# pcb_telemetria.net
KiCad netlist of a schematic drawn in EAGLE
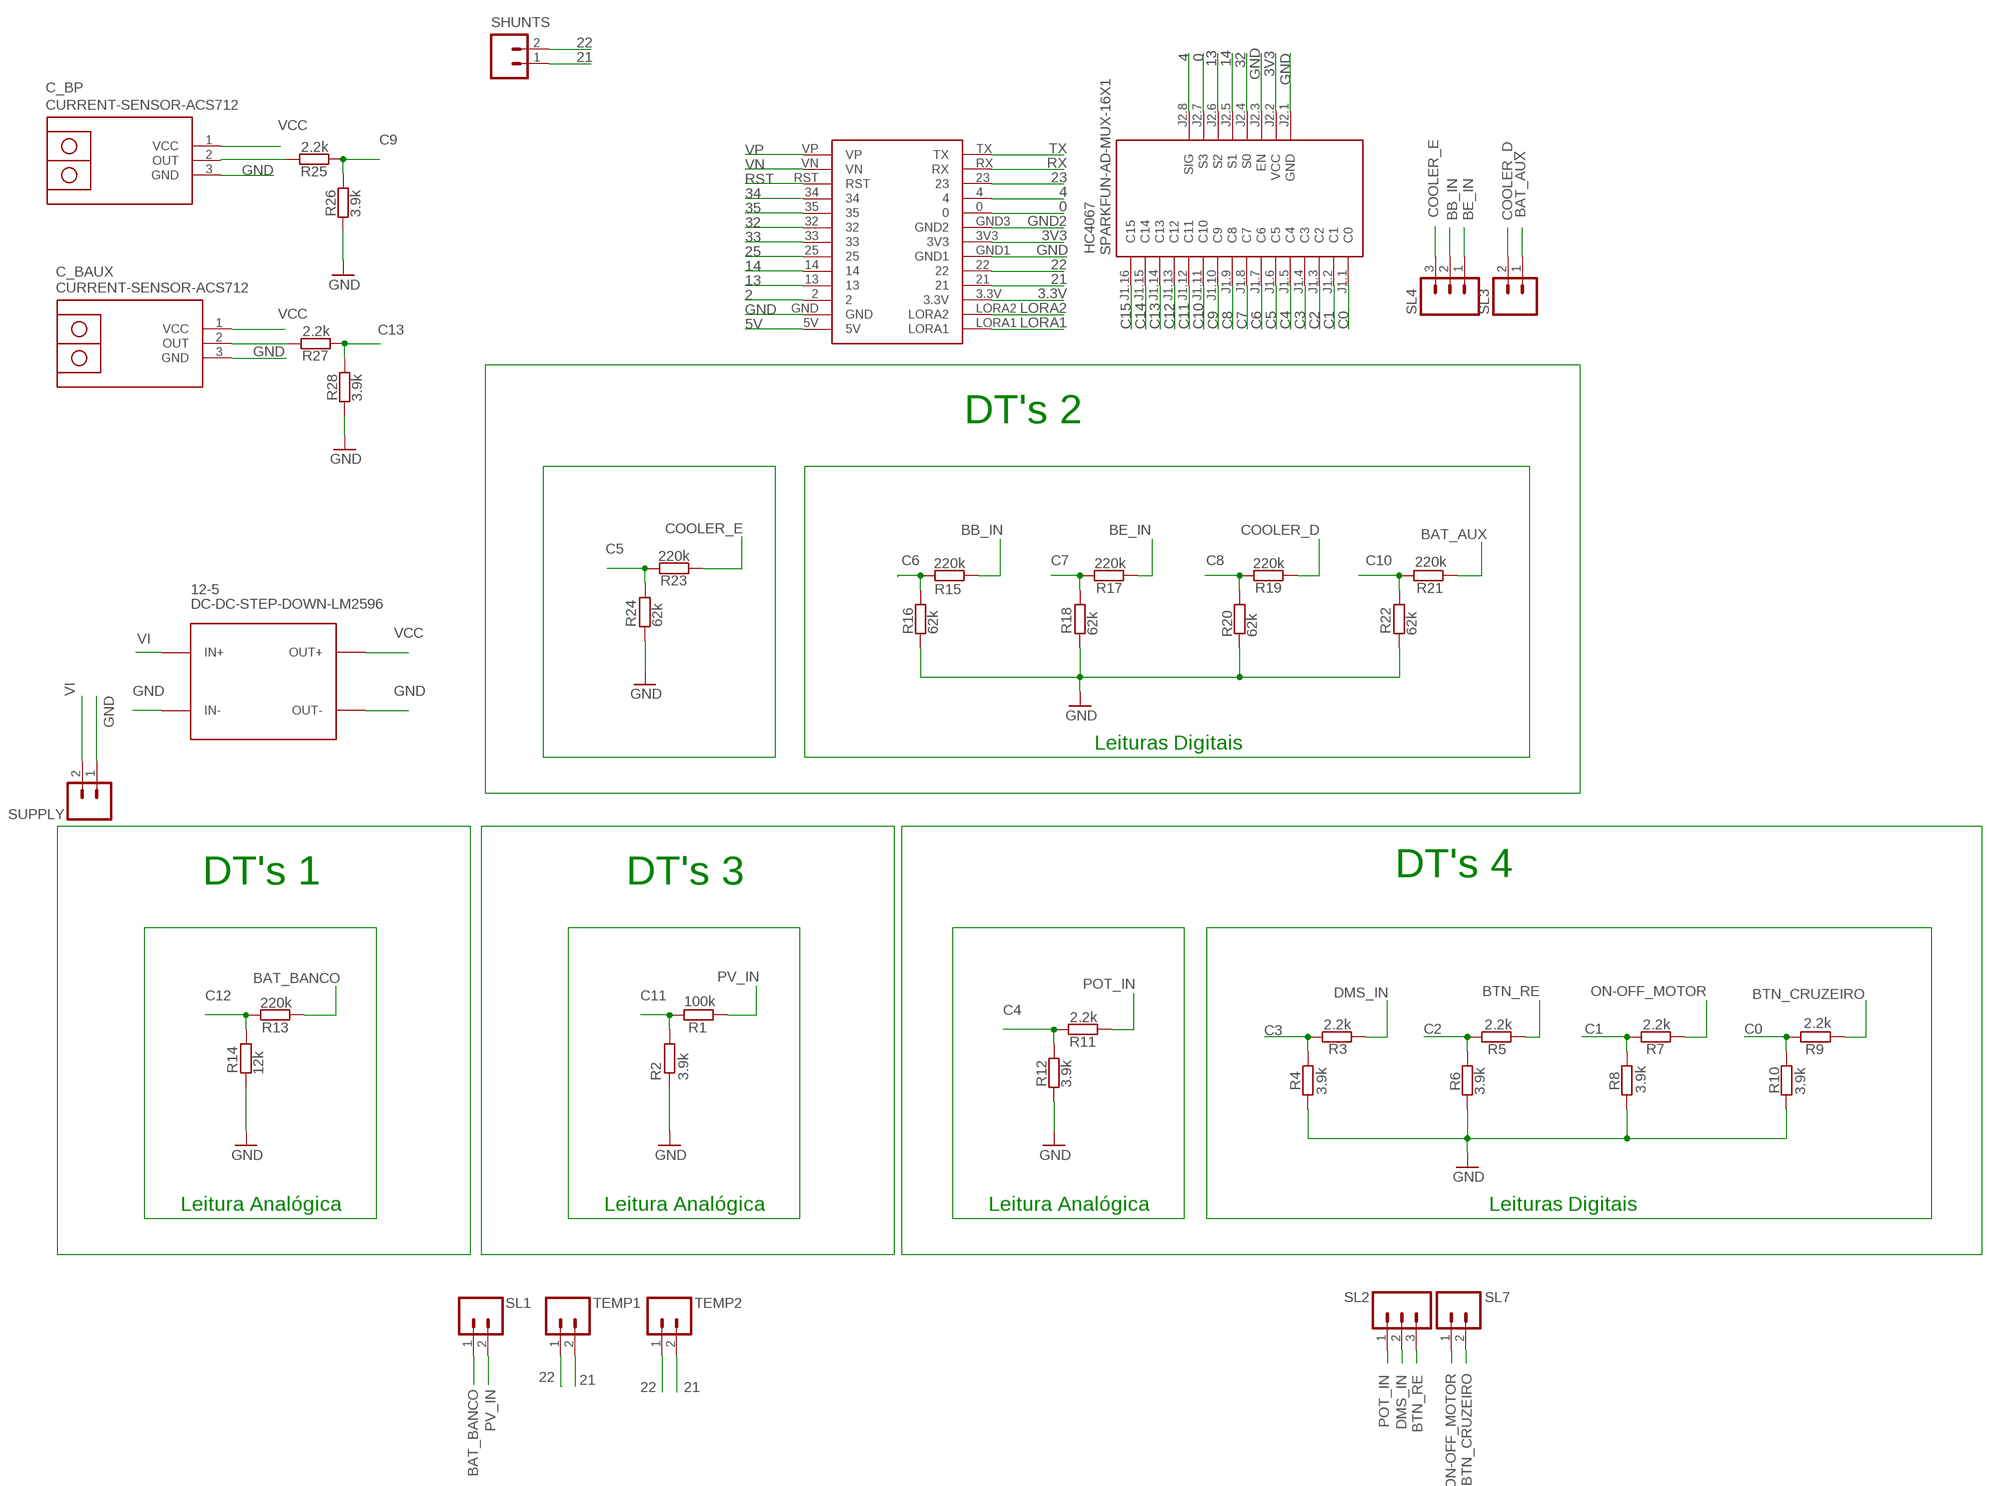
[diagram p0: schematic, sheet 1]

(export (version "E")
  (design (tool "Eeschema 10.0.6"))
  (components
    (comp (ref "12-5")
      (value "DC-DC-STEP-DOWN-LM2596")
      (footprint "eagle-import:DC-DC-STEP-DOWN-LM2596")
      (libsource (lib "eagle-import") (part "DC-DC-STEP-DOWN-LM2596"))
    )
    (comp (ref "C_BAUX")
      (value "CURRENT-SENSOR-ACS712")
      (footprint "eagle-import:CURRENT-SENSOR-ACS712")
      (libsource (lib "eagle-import") (part "CURRENT-SENSOR-ACS712"))
    )
    (comp (ref "C_BP")
      (value "CURRENT-SENSOR-ACS712")
      (footprint "eagle-import:CURRENT-SENSOR-ACS712")
      (libsource (lib "eagle-import") (part "CURRENT-SENSOR-ACS712"))
    )
    (comp (ref "HC4067")
      (value "SPARKFUN-AD-MUX-16X1")
      (footprint "eagle-import:SPARKFUN-AD-MUX-16X1")
      (libsource (lib "eagle-import") (part "SPARKFUN-AD-MUX-16X1"))
    )
    (comp (ref "R1")
      (value "100k")
      (footprint "eagle-import:0204_7")
      (libsource (lib "eagle-import") (part "R-EU_0204/7"))
    )
    (comp (ref "R2")
      (value "3.9k")
      (footprint "eagle-import:0204_7")
      (libsource (lib "eagle-import") (part "R-EU_0204/7"))
    )
    (comp (ref "R3")
      (value "2.2k")
      (footprint "eagle-import:0204_7")
      (libsource (lib "eagle-import") (part "R-EU_0204/7"))
    )
    (comp (ref "R4")
      (value "3.9k")
      (footprint "eagle-import:0204_7")
      (libsource (lib "eagle-import") (part "R-EU_0204/7"))
    )
    (comp (ref "R5")
      (value "2.2k")
      (footprint "eagle-import:0204_7")
      (libsource (lib "eagle-import") (part "R-EU_0204/7"))
    )
    (comp (ref "R6")
      (value "3.9k")
      (footprint "eagle-import:0204_7")
      (libsource (lib "eagle-import") (part "R-EU_0204/7"))
    )
    (comp (ref "R7")
      (value "2.2k")
      (footprint "eagle-import:0204_7")
      (libsource (lib "eagle-import") (part "R-EU_0204/7"))
    )
    (comp (ref "R8")
      (value "3.9k")
      (footprint "eagle-import:0204_7")
      (libsource (lib "eagle-import") (part "R-EU_0204/7"))
    )
    (comp (ref "R9")
      (value "2.2k")
      (footprint "eagle-import:0204_7")
      (libsource (lib "eagle-import") (part "R-EU_0204/7"))
    )
    (comp (ref "R10")
      (value "3.9k")
      (footprint "eagle-import:0204_7")
      (libsource (lib "eagle-import") (part "R-EU_0204/7"))
    )
    (comp (ref "R11")
      (value "2.2k")
      (footprint "eagle-import:0204_7")
      (libsource (lib "eagle-import") (part "R-EU_0204/7"))
    )
    (comp (ref "R12")
      (value "3.9k")
      (footprint "eagle-import:0204_7")
      (libsource (lib "eagle-import") (part "R-EU_0204/7"))
    )
    (comp (ref "R13")
      (value "220k")
      (footprint "eagle-import:0204_7")
      (libsource (lib "eagle-import") (part "R-EU_0204/7"))
    )
    (comp (ref "R14")
      (value "12k")
      (footprint "eagle-import:0204_7")
      (libsource (lib "eagle-import") (part "R-EU_0204/7"))
    )
    (comp (ref "R15")
      (value "220k")
      (footprint "eagle-import:0204_7")
      (libsource (lib "eagle-import") (part "R-EU_0204/7"))
    )
    (comp (ref "R16")
      (value "62k")
      (footprint "eagle-import:0204_7")
      (libsource (lib "eagle-import") (part "R-EU_0204/7"))
    )
    (comp (ref "R17")
      (value "220k")
      (footprint "eagle-import:0204_7")
      (libsource (lib "eagle-import") (part "R-EU_0204/7"))
    )
    (comp (ref "R18")
      (value "62k")
      (footprint "eagle-import:0204_7")
      (libsource (lib "eagle-import") (part "R-EU_0204/7"))
    )
    (comp (ref "R19")
      (value "220k")
      (footprint "eagle-import:0204_7")
      (libsource (lib "eagle-import") (part "R-EU_0204/7"))
    )
    (comp (ref "R20")
      (value "62k")
      (footprint "eagle-import:0204_7")
      (libsource (lib "eagle-import") (part "R-EU_0204/7"))
    )
    (comp (ref "R21")
      (value "220k")
      (footprint "eagle-import:0204_7")
      (libsource (lib "eagle-import") (part "R-EU_0204/7"))
    )
    (comp (ref "R22")
      (value "62k")
      (footprint "eagle-import:0204_7")
      (libsource (lib "eagle-import") (part "R-EU_0204/7"))
    )
    (comp (ref "R23")
      (value "220k")
      (footprint "eagle-import:0204_7")
      (libsource (lib "eagle-import") (part "R-EU_0204/7"))
    )
    (comp (ref "R24")
      (value "62k")
      (footprint "eagle-import:0204_7")
      (libsource (lib "eagle-import") (part "R-EU_0204/7"))
    )
    (comp (ref "R25")
      (value "2.2k")
      (footprint "eagle-import:0204_7")
      (libsource (lib "eagle-import") (part "R-EU_0204/7"))
    )
    (comp (ref "R26")
      (value "3.9k")
      (footprint "eagle-import:0204_7")
      (libsource (lib "eagle-import") (part "R-EU_0204/7"))
    )
    (comp (ref "R27")
      (value "2.2k")
      (footprint "eagle-import:0204_7")
      (libsource (lib "eagle-import") (part "R-EU_0204/7"))
    )
    (comp (ref "R28")
      (value "3.9k")
      (footprint "eagle-import:0204_7")
      (libsource (lib "eagle-import") (part "R-EU_0204/7"))
    )
    (comp (ref "SHUNTS")
      (value "M02")
      (footprint "eagle-import:02P")
      (libsource (lib "eagle-import") (part "M02"))
    )
    (comp (ref "SL1")
      (value "M02")
      (footprint "eagle-import:02P")
      (libsource (lib "eagle-import") (part "M02"))
    )
    (comp (ref "SL2")
      (value "M03")
      (footprint "eagle-import:03P")
      (libsource (lib "eagle-import") (part "M03"))
    )
    (comp (ref "SL3")
      (value "M02")
      (footprint "eagle-import:02P")
      (libsource (lib "eagle-import") (part "M02"))
    )
    (comp (ref "SL4")
      (value "M03")
      (footprint "eagle-import:03P")
      (libsource (lib "eagle-import") (part "M03"))
    )
    (comp (ref "SL7")
      (value "M02")
      (footprint "eagle-import:02P")
      (libsource (lib "eagle-import") (part "M02"))
    )
    (comp (ref "SUPPLY")
      (value "M02")
      (footprint "eagle-import:02P")
      (libsource (lib "eagle-import") (part "M02"))
    )
    (comp (ref "TEMP1")
      (value "M02")
      (footprint "eagle-import:02P")
      (libsource (lib "eagle-import") (part "M02"))
    )
    (comp (ref "TEMP2")
      (value "M02")
      (footprint "eagle-import:02P")
      (libsource (lib "eagle-import") (part "M02"))
    )
    (comp (ref "U$1")
      (value "TTGOBEAM")
      (footprint "eagle-import:TTGOBEAM")
      (libsource (lib "eagle-import") (part "TTGOBEAM"))
    )
  )
  (nets
    (net (code "1") (name "/0") (class "Default")
      (node (ref "HC4067") (pin "J2.7") (pinfunction "S3_J2.7") (pintype "bidirectional"))
      (node (ref "U$1") (pin "0") (pinfunction "0_0") (pintype "bidirectional"))
    )
    (net (code "2") (name "/2") (class "Default")
      (node (ref "U$1") (pin "2") (pinfunction "2_2") (pintype "bidirectional"))
    )
    (net (code "3") (name "/3.3V") (class "Default")
      (node (ref "U$1") (pin "3.3V") (pinfunction "3.3V_3.3V") (pintype "bidirectional"))
    )
    (net (code "4") (name "/3V3") (class "Default")
      (node (ref "HC4067") (pin "J2.2") (pinfunction "VCC_J2.2") (pintype "power_in"))
      (node (ref "U$1") (pin "3V3") (pinfunction "3V3_3V3") (pintype "bidirectional"))
    )
    (net (code "5") (name "/4") (class "Default")
      (node (ref "HC4067") (pin "J2.8") (pinfunction "SIG_J2.8") (pintype "bidirectional"))
      (node (ref "U$1") (pin "4") (pinfunction "4_4") (pintype "bidirectional"))
    )
    (net (code "6") (name "/5V") (class "Default")
      (node (ref "U$1") (pin "5V") (pinfunction "5V_5V") (pintype "bidirectional"))
    )
    (net (code "7") (name "/13") (class "Default")
      (node (ref "HC4067") (pin "J2.6") (pinfunction "S2_J2.6") (pintype "bidirectional"))
      (node (ref "U$1") (pin "13") (pinfunction "13_13") (pintype "bidirectional"))
    )
    (net (code "8") (name "/14") (class "Default")
      (node (ref "HC4067") (pin "J2.5") (pinfunction "S1_J2.5") (pintype "bidirectional"))
      (node (ref "U$1") (pin "14") (pinfunction "14_14") (pintype "bidirectional"))
    )
    (net (code "9") (name "/21") (class "Default")
      (node (ref "SHUNTS") (pin "1") (pinfunction "1_1") (pintype "passive"))
      (node (ref "TEMP1") (pin "2") (pinfunction "2_2") (pintype "passive"))
      (node (ref "TEMP2") (pin "2") (pinfunction "2_2") (pintype "passive"))
      (node (ref "U$1") (pin "21") (pinfunction "21_21") (pintype "bidirectional"))
    )
    (net (code "10") (name "/22") (class "Default")
      (node (ref "SHUNTS") (pin "2") (pinfunction "2_2") (pintype "passive"))
      (node (ref "TEMP1") (pin "1") (pinfunction "1_1") (pintype "passive"))
      (node (ref "TEMP2") (pin "1") (pinfunction "1_1") (pintype "passive"))
      (node (ref "U$1") (pin "22") (pinfunction "22_22") (pintype "bidirectional"))
    )
    (net (code "11") (name "/23") (class "Default")
      (node (ref "U$1") (pin "23") (pinfunction "23_23") (pintype "bidirectional"))
    )
    (net (code "12") (name "/25") (class "Default")
      (node (ref "U$1") (pin "25") (pinfunction "25_25") (pintype "bidirectional"))
    )
    (net (code "13") (name "/32") (class "Default")
      (node (ref "HC4067") (pin "J2.4") (pinfunction "S0_J2.4") (pintype "bidirectional"))
      (node (ref "U$1") (pin "32") (pinfunction "32_32") (pintype "bidirectional"))
    )
    (net (code "14") (name "/33") (class "Default")
      (node (ref "U$1") (pin "33") (pinfunction "33_33") (pintype "bidirectional"))
    )
    (net (code "15") (name "/34") (class "Default")
      (node (ref "U$1") (pin "34") (pinfunction "34_34") (pintype "bidirectional"))
    )
    (net (code "16") (name "/35") (class "Default")
      (node (ref "U$1") (pin "35") (pinfunction "35_35") (pintype "bidirectional"))
    )
    (net (code "17") (name "/BAT_AUX") (class "Default")
      (node (ref "R21") (pin "2") (pinfunction "2_2") (pintype "passive"))
      (node (ref "SL3") (pin "1") (pinfunction "1_1") (pintype "passive"))
    )
    (net (code "18") (name "/BAT_BANCO") (class "Default")
      (node (ref "R13") (pin "2") (pinfunction "2_2") (pintype "passive"))
      (node (ref "SL1") (pin "1") (pinfunction "1_1") (pintype "passive"))
    )
    (net (code "19") (name "/BB_IN") (class "Default")
      (node (ref "R15") (pin "1") (pinfunction "1_1") (pintype "passive"))
      (node (ref "SL4") (pin "2") (pinfunction "2_2") (pintype "passive"))
    )
    (net (code "20") (name "/BE_IN") (class "Default")
      (node (ref "R17") (pin "2") (pinfunction "2_2") (pintype "passive"))
      (node (ref "SL4") (pin "1") (pinfunction "1_1") (pintype "passive"))
    )
    (net (code "21") (name "/BTN_CRUZEIRO") (class "Default")
      (node (ref "R9") (pin "2") (pinfunction "2_2") (pintype "passive"))
      (node (ref "SL7") (pin "2") (pinfunction "2_2") (pintype "passive"))
    )
    (net (code "22") (name "/BTN_RE") (class "Default")
      (node (ref "R5") (pin "2") (pinfunction "2_2") (pintype "passive"))
      (node (ref "SL2") (pin "3") (pinfunction "3_3") (pintype "passive"))
    )
    (net (code "23") (name "/C0") (class "Default")
      (node (ref "HC4067") (pin "J1.1") (pinfunction "C0_J1.1") (pintype "bidirectional"))
      (node (ref "R10") (pin "2") (pinfunction "2_2") (pintype "passive"))
      (node (ref "R9") (pin "1") (pinfunction "1_1") (pintype "passive"))
    )
    (net (code "24") (name "/C1") (class "Default")
      (node (ref "HC4067") (pin "J1.2") (pinfunction "C1_J1.2") (pintype "bidirectional"))
      (node (ref "R7") (pin "2") (pinfunction "2_2") (pintype "passive"))
      (node (ref "R8") (pin "1") (pinfunction "1_1") (pintype "passive"))
    )
    (net (code "25") (name "/C2") (class "Default")
      (node (ref "HC4067") (pin "J1.3") (pinfunction "C2_J1.3") (pintype "bidirectional"))
      (node (ref "R5") (pin "1") (pinfunction "1_1") (pintype "passive"))
      (node (ref "R6") (pin "2") (pinfunction "2_2") (pintype "passive"))
    )
    (net (code "26") (name "/C3") (class "Default")
      (node (ref "HC4067") (pin "J1.4") (pinfunction "C3_J1.4") (pintype "bidirectional"))
      (node (ref "R3") (pin "2") (pinfunction "2_2") (pintype "passive"))
      (node (ref "R4") (pin "1") (pinfunction "1_1") (pintype "passive"))
    )
    (net (code "27") (name "/C4") (class "Default")
      (node (ref "HC4067") (pin "J1.5") (pinfunction "C4_J1.5") (pintype "bidirectional"))
      (node (ref "R11") (pin "2") (pinfunction "2_2") (pintype "passive"))
      (node (ref "R12") (pin "1") (pinfunction "1_1") (pintype "passive"))
    )
    (net (code "28") (name "/C5") (class "Default")
      (node (ref "HC4067") (pin "J1.6") (pinfunction "C5_J1.6") (pintype "bidirectional"))
      (node (ref "R23") (pin "2") (pinfunction "2_2") (pintype "passive"))
      (node (ref "R24") (pin "1") (pinfunction "1_1") (pintype "passive"))
    )
    (net (code "29") (name "/C6") (class "Default")
      (node (ref "HC4067") (pin "J1.7") (pinfunction "C6_J1.7") (pintype "bidirectional"))
      (node (ref "R15") (pin "2") (pinfunction "2_2") (pintype "passive"))
      (node (ref "R16") (pin "1") (pinfunction "1_1") (pintype "passive"))
    )
    (net (code "30") (name "/C7") (class "Default")
      (node (ref "HC4067") (pin "J1.8") (pinfunction "C7_J1.8") (pintype "bidirectional"))
      (node (ref "R17") (pin "1") (pinfunction "1_1") (pintype "passive"))
      (node (ref "R18") (pin "2") (pinfunction "2_2") (pintype "passive"))
    )
    (net (code "31") (name "/C8") (class "Default")
      (node (ref "HC4067") (pin "J1.9") (pinfunction "C8_J1.9") (pintype "bidirectional"))
      (node (ref "R19") (pin "2") (pinfunction "2_2") (pintype "passive"))
      (node (ref "R20") (pin "1") (pinfunction "1_1") (pintype "passive"))
    )
    (net (code "32") (name "/C9") (class "Default")
      (node (ref "HC4067") (pin "J1.10") (pinfunction "C9_J1.10") (pintype "bidirectional"))
      (node (ref "R25") (pin "1") (pinfunction "1_1") (pintype "passive"))
      (node (ref "R26") (pin "1") (pinfunction "1_1") (pintype "passive"))
    )
    (net (code "33") (name "/C10") (class "Default")
      (node (ref "HC4067") (pin "J1.11") (pinfunction "C10_J1.11") (pintype "bidirectional"))
      (node (ref "R21") (pin "1") (pinfunction "1_1") (pintype "passive"))
      (node (ref "R22") (pin "2") (pinfunction "2_2") (pintype "passive"))
    )
    (net (code "34") (name "/C11") (class "Default")
      (node (ref "HC4067") (pin "J1.12") (pinfunction "C11_J1.12") (pintype "bidirectional"))
      (node (ref "R1") (pin "1") (pinfunction "1_1") (pintype "passive"))
      (node (ref "R2") (pin "2") (pinfunction "2_2") (pintype "passive"))
    )
    (net (code "35") (name "/C12") (class "Default")
      (node (ref "HC4067") (pin "J1.13") (pinfunction "C12_J1.13") (pintype "bidirectional"))
      (node (ref "R13") (pin "1") (pinfunction "1_1") (pintype "passive"))
      (node (ref "R14") (pin "2") (pinfunction "2_2") (pintype "passive"))
    )
    (net (code "36") (name "/C13") (class "Default")
      (node (ref "HC4067") (pin "J1.14") (pinfunction "C13_J1.14") (pintype "bidirectional"))
      (node (ref "R27") (pin "1") (pinfunction "1_1") (pintype "passive"))
      (node (ref "R28") (pin "1") (pinfunction "1_1") (pintype "passive"))
    )
    (net (code "37") (name "/C14") (class "Default")
      (node (ref "HC4067") (pin "J1.15") (pinfunction "C14_J1.15") (pintype "bidirectional"))
    )
    (net (code "38") (name "/C15") (class "Default")
      (node (ref "HC4067") (pin "J1.16") (pinfunction "C15_J1.16") (pintype "bidirectional"))
    )
    (net (code "39") (name "/COOLER_D") (class "Default")
      (node (ref "R19") (pin "1") (pinfunction "1_1") (pintype "passive"))
      (node (ref "SL3") (pin "2") (pinfunction "2_2") (pintype "passive"))
    )
    (net (code "40") (name "/COOLER_E") (class "Default")
      (node (ref "R23") (pin "1") (pinfunction "1_1") (pintype "passive"))
      (node (ref "SL4") (pin "3") (pinfunction "3_3") (pintype "passive"))
    )
    (net (code "41") (name "/DMS_IN") (class "Default")
      (node (ref "R3") (pin "1") (pinfunction "1_1") (pintype "passive"))
      (node (ref "SL2") (pin "2") (pinfunction "2_2") (pintype "passive"))
    )
    (net (code "42") (name "/GND2") (class "Default")
      (node (ref "U$1") (pin "GND3") (pinfunction "GND2_GND3") (pintype "bidirectional"))
    )
    (net (code "43") (name "/LORA1") (class "Default")
      (node (ref "U$1") (pin "LORA1") (pinfunction "LORA1_LORA1") (pintype "bidirectional"))
    )
    (net (code "44") (name "/LORA2") (class "Default")
      (node (ref "U$1") (pin "LORA2") (pinfunction "LORA2_LORA2") (pintype "bidirectional"))
    )
    (net (code "45") (name "/ON-OFF_MOTOR") (class "Default")
      (node (ref "R7") (pin "1") (pinfunction "1_1") (pintype "passive"))
      (node (ref "SL7") (pin "1") (pinfunction "1_1") (pintype "passive"))
    )
    (net (code "46") (name "/POT_IN") (class "Default")
      (node (ref "R11") (pin "1") (pinfunction "1_1") (pintype "passive"))
      (node (ref "SL2") (pin "1") (pinfunction "1_1") (pintype "passive"))
    )
    (net (code "47") (name "/PV_IN") (class "Default")
      (node (ref "R1") (pin "2") (pinfunction "2_2") (pintype "passive"))
      (node (ref "SL1") (pin "2") (pinfunction "2_2") (pintype "passive"))
    )
    (net (code "48") (name "/RST") (class "Default")
      (node (ref "U$1") (pin "RST") (pinfunction "RST_RST") (pintype "bidirectional"))
    )
    (net (code "49") (name "/RX") (class "Default")
      (node (ref "U$1") (pin "RX") (pinfunction "RX_RX") (pintype "bidirectional"))
    )
    (net (code "50") (name "/TX") (class "Default")
      (node (ref "U$1") (pin "TX") (pinfunction "TX_TX") (pintype "bidirectional"))
    )
    (net (code "51") (name "/VCC") (class "Default")
      (node (ref "12-5") (pin "OUT+") (pinfunction "OUT+_OUT+") (pintype "bidirectional"))
      (node (ref "C_BAUX") (pin "1") (pinfunction "VCC_1") (pintype "power_in"))
      (node (ref "C_BP") (pin "1") (pinfunction "VCC_1") (pintype "power_in"))
    )
    (net (code "52") (name "/VI") (class "Default")
      (node (ref "12-5") (pin "IN+") (pinfunction "IN+_IN+") (pintype "bidirectional"))
      (node (ref "SUPPLY") (pin "2") (pinfunction "2_2") (pintype "passive"))
    )
    (net (code "53") (name "/VN") (class "Default")
      (node (ref "U$1") (pin "VN") (pinfunction "VN_VN") (pintype "bidirectional"))
    )
    (net (code "54") (name "/VP") (class "Default")
      (node (ref "U$1") (pin "VP") (pinfunction "VP_VP") (pintype "bidirectional"))
    )
    (net (code "55") (name "GND") (class "Default")
      (node (ref "12-5") (pin "IN-") (pinfunction "IN-_IN-") (pintype "bidirectional"))
      (node (ref "12-5") (pin "OUT-") (pinfunction "OUT-_OUT-") (pintype "bidirectional"))
      (node (ref "C_BAUX") (pin "3") (pinfunction "GND_3") (pintype "power_in"))
      (node (ref "C_BP") (pin "3") (pinfunction "GND_3") (pintype "power_in"))
      (node (ref "HC4067") (pin "J2.1") (pinfunction "GND_J2.1") (pintype "power_in"))
      (node (ref "HC4067") (pin "J2.3") (pinfunction "EN_J2.3") (pintype "input"))
      (node (ref "R10") (pin "1") (pinfunction "1_1") (pintype "passive"))
      (node (ref "R12") (pin "2") (pinfunction "2_2") (pintype "passive"))
      (node (ref "R14") (pin "1") (pinfunction "1_1") (pintype "passive"))
      (node (ref "R16") (pin "2") (pinfunction "2_2") (pintype "passive"))
      (node (ref "R18") (pin "1") (pinfunction "1_1") (pintype "passive"))
      (node (ref "R2") (pin "1") (pinfunction "1_1") (pintype "passive"))
      (node (ref "R20") (pin "2") (pinfunction "2_2") (pintype "passive"))
      (node (ref "R22") (pin "1") (pinfunction "1_1") (pintype "passive"))
      (node (ref "R24") (pin "2") (pinfunction "2_2") (pintype "passive"))
      (node (ref "R26") (pin "2") (pinfunction "2_2") (pintype "passive"))
      (node (ref "R28") (pin "2") (pinfunction "2_2") (pintype "passive"))
      (node (ref "R4") (pin "2") (pinfunction "2_2") (pintype "passive"))
      (node (ref "R6") (pin "1") (pinfunction "1_1") (pintype "passive"))
      (node (ref "R8") (pin "2") (pinfunction "2_2") (pintype "passive"))
      (node (ref "SUPPLY") (pin "1") (pinfunction "1_1") (pintype "passive"))
      (node (ref "U$1") (pin "GND") (pinfunction "GND_GND") (pintype "bidirectional"))
      (node (ref "U$1") (pin "GND1") (pinfunction "GND1_GND1") (pintype "bidirectional"))
    )
    (net (code "56") (name "Net-(C_BAUX-OUT)") (class "Default")
      (node (ref "C_BAUX") (pin "2") (pinfunction "OUT_2") (pintype "output"))
      (node (ref "R27") (pin "2") (pinfunction "2_2") (pintype "passive"))
    )
    (net (code "57") (name "Net-(C_BP-OUT)") (class "Default")
      (node (ref "C_BP") (pin "2") (pinfunction "OUT_2") (pintype "output"))
      (node (ref "R25") (pin "2") (pinfunction "2_2") (pintype "passive"))
    )
  )
)
